# PortBreakoutCapacitive_r2.net
KiCad netlist of a schematic drawn in EAGLE
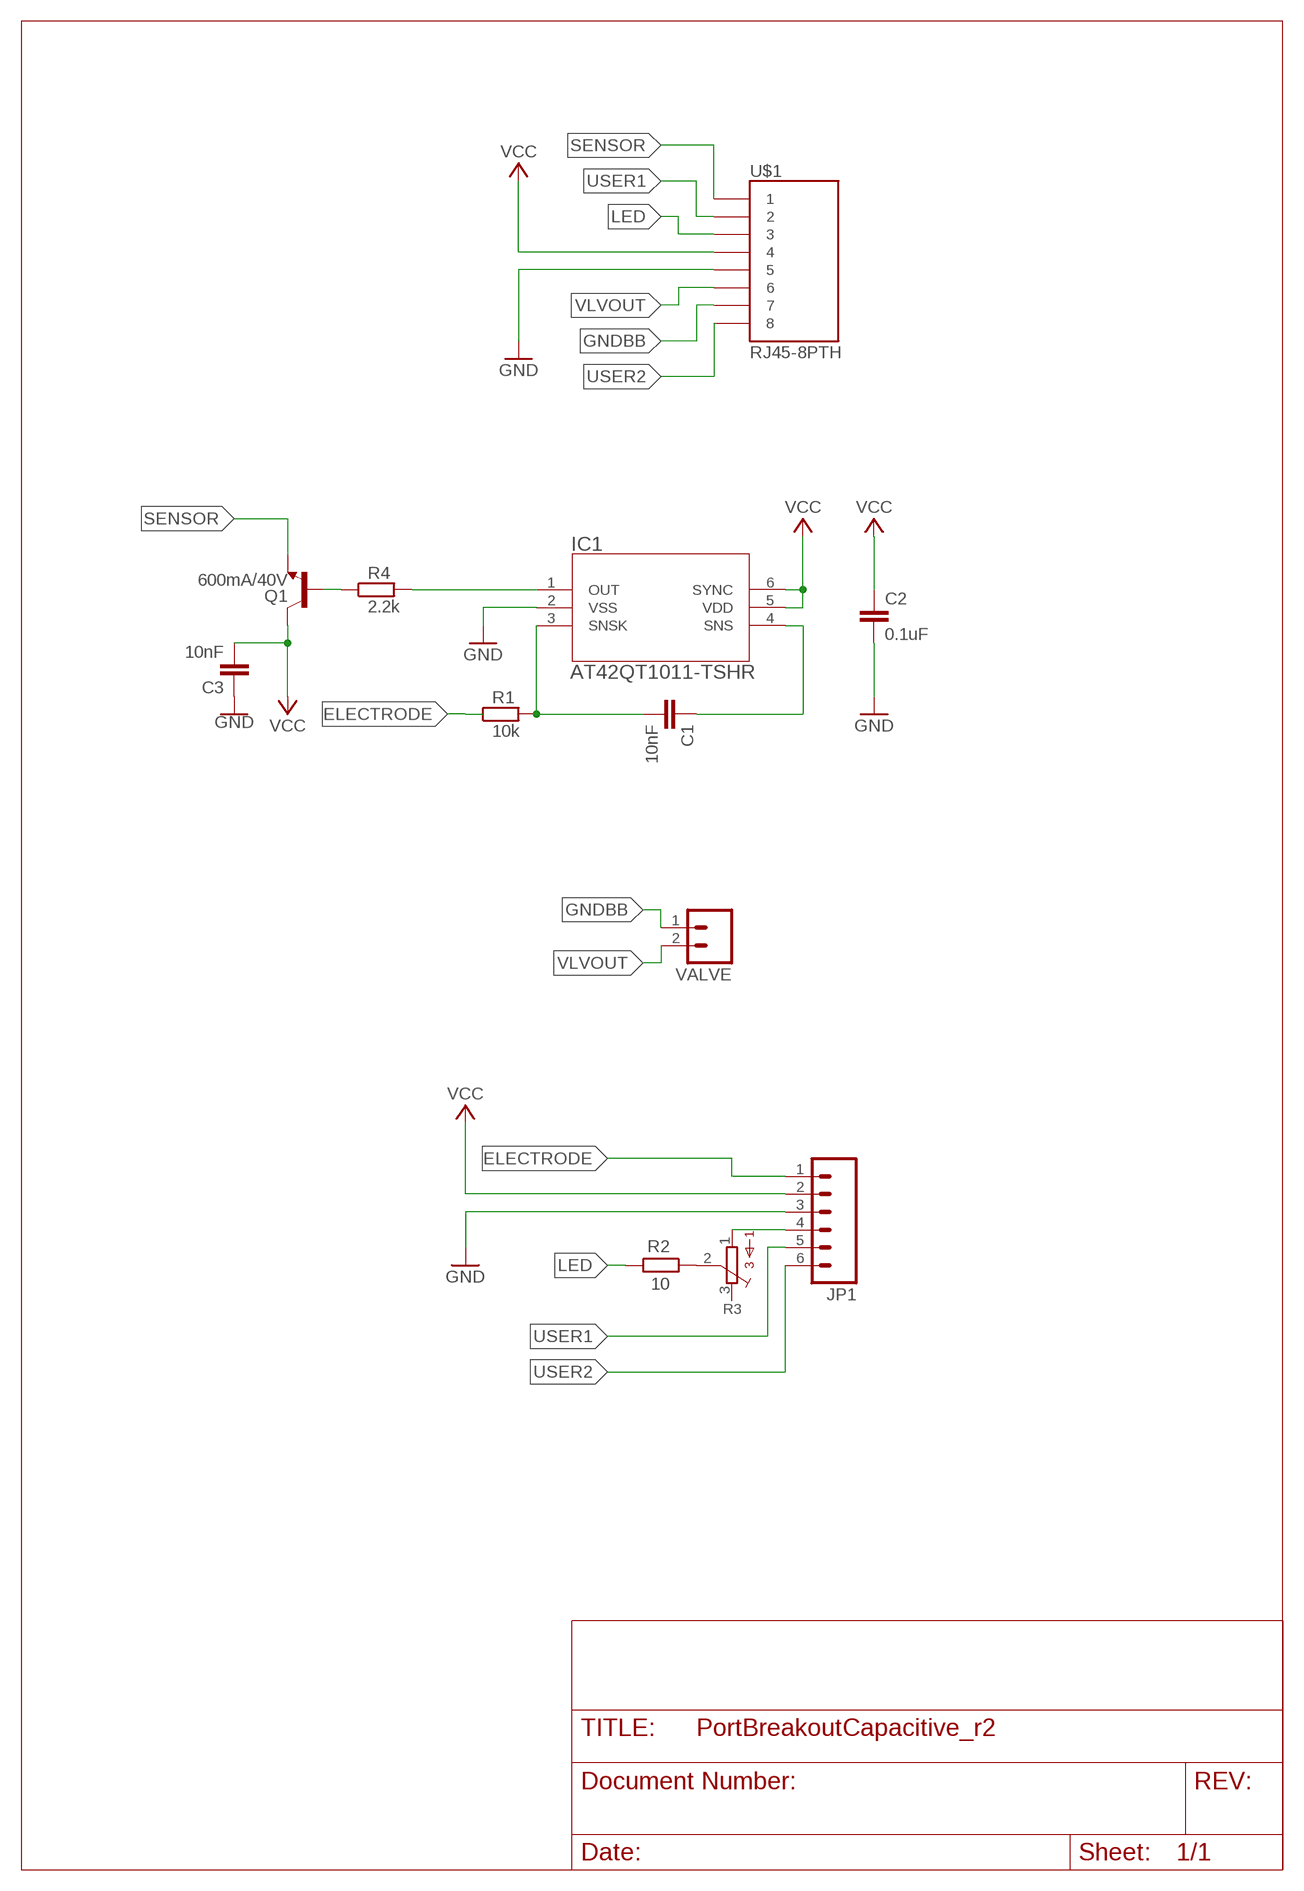
[diagram p0: schematic, sheet 1]

(export (version "E")
  (design (tool "Eeschema 10.0.6"))
  (components
    (comp (ref "C1")
      (value "10nF")
      (footprint "eagle-import:C1206")
      (libsource (lib "eagle-import") (part "C-EUC1206"))
    )
    (comp (ref "C2")
      (value "0.1uF")
      (footprint "eagle-import:C1206")
      (libsource (lib "eagle-import") (part "C-EUC1206"))
    )
    (comp (ref "C3")
      (value "10nF")
      (footprint "eagle-import:C1206")
      (libsource (lib "eagle-import") (part "C-EUC1206"))
    )
    (comp (ref "IC1")
      (value "AT42QT1011-TSHR")
      (footprint "eagle-import:6ST1_ATM")
      (fields (field (name "MANUFACTURER_PART_NUMBER") "AT42QT1010-TSHR"))
      (libsource (lib "eagle-import") (part "AT42QT1010-TSHR"))
    )
    (comp (ref "JP1")
      (value "M063.5MM-6")
      (footprint "eagle-import:SCREWTERMINAL-3.5MM-6")
      (libsource (lib "eagle-import") (part "M063.5MM-6"))
    )
    (comp (ref "Q1")
      (value "600mA/40V")
      (footprint "eagle-import:SOT23-3")
      (libsource (lib "eagle-import") (part "TRANS_NPN-MMBT2222AL"))
    )
    (comp (ref "R1")
      (value "10k")
      (footprint "eagle-import:R1206")
      (libsource (lib "eagle-import") (part "R-EU_R1206"))
    )
    (comp (ref "R2")
      (value "10")
      (footprint "eagle-import:R1206")
      (libsource (lib "eagle-import") (part "R-EU_R1206"))
    )
    (comp (ref "R3")
      (value "3362R")
      (footprint "eagle-import:3362R")
      (libsource (lib "eagle-import") (part "3362R"))
    )
    (comp (ref "R4")
      (value "2.2k")
      (footprint "eagle-import:R1206")
      (libsource (lib "eagle-import") (part "R-EU_R1206"))
    )
    (comp (ref "U$1")
      (value "RJ45-8PTH")
      (footprint "eagle-import:RJ45-8")
      (libsource (lib "eagle-import") (part "RJ45-8PTH"))
    )
    (comp (ref "VALVE")
      (value "M023.5MM_LOCK")
      (footprint "eagle-import:SCREWTERMINAL-3.5MM-2_LOCK")
      (libsource (lib "eagle-import") (part "M023.5MM_LOCK"))
    )
  )
  (nets
    (net (code "1") (name "ELECTRODE") (class "Default")
      (node (ref "JP1") (pin "1") (pinfunction "1_1") (pintype "passive"))
      (node (ref "R1") (pin "1") (pinfunction "1_1") (pintype "passive"))
    )
    (net (code "2") (name "GND") (class "Default")
      (node (ref "C2") (pin "2") (pinfunction "2_2") (pintype "passive"))
      (node (ref "C3") (pin "1") (pinfunction "1_1") (pintype "passive"))
      (node (ref "IC1") (pin "2") (pinfunction "VSS_2") (pintype "power_in"))
      (node (ref "JP1") (pin "3") (pinfunction "3_3") (pintype "passive"))
      (node (ref "U$1") (pin "5") (pinfunction "5_5") (pintype "bidirectional"))
    )
    (net (code "3") (name "GNDBB") (class "Default")
      (node (ref "U$1") (pin "7") (pinfunction "7_7") (pintype "bidirectional"))
      (node (ref "VALVE") (pin "1") (pinfunction "1_1") (pintype "passive"))
    )
    (net (code "4") (name "LED") (class "Default")
      (node (ref "R2") (pin "2") (pinfunction "2_2") (pintype "passive"))
      (node (ref "U$1") (pin "3") (pinfunction "3_3") (pintype "bidirectional"))
    )
    (net (code "5") (name "Net-(IC1-OUT)") (class "Default")
      (node (ref "IC1") (pin "1") (pinfunction "OUT_1") (pintype "output"))
      (node (ref "R4") (pin "2") (pinfunction "2_2") (pintype "passive"))
    )
    (net (code "6") (name "Net-(IC1-SNS)") (class "Default")
      (node (ref "C1") (pin "1") (pinfunction "1_1") (pintype "passive"))
      (node (ref "IC1") (pin "4") (pinfunction "SNS_4") (pintype "bidirectional"))
    )
    (net (code "7") (name "Net-(IC1-SNSK)") (class "Default")
      (node (ref "C1") (pin "2") (pinfunction "2_2") (pintype "passive"))
      (node (ref "IC1") (pin "3") (pinfunction "SNSK_3") (pintype "bidirectional"))
      (node (ref "R1") (pin "2") (pinfunction "2_2") (pintype "passive"))
    )
    (net (code "8") (name "Net-(JP1-Pad4)") (class "Default")
      (node (ref "JP1") (pin "4") (pinfunction "4_4") (pintype "passive"))
      (node (ref "R3") (pin "1") (pinfunction "1_1") (pintype "passive"))
    )
    (net (code "9") (name "Net-(Q1-B)") (class "Default")
      (node (ref "Q1") (pin "1") (pinfunction "B_1") (pintype "passive"))
      (node (ref "R4") (pin "1") (pinfunction "1_1") (pintype "passive"))
    )
    (net (code "10") (name "Net-(R2-Pad1)") (class "Default")
      (node (ref "R2") (pin "1") (pinfunction "1_1") (pintype "passive"))
      (node (ref "R3") (pin "2") (pinfunction "2_2") (pintype "passive"))
    )
    (net (code "11") (name "SENSOR") (class "Default")
      (node (ref "Q1") (pin "2") (pinfunction "E_2") (pintype "passive"))
      (node (ref "U$1") (pin "1") (pinfunction "1_1") (pintype "bidirectional"))
    )
    (net (code "12") (name "USER1") (class "Default")
      (node (ref "JP1") (pin "5") (pinfunction "5_5") (pintype "passive"))
      (node (ref "U$1") (pin "2") (pinfunction "2_2") (pintype "bidirectional"))
    )
    (net (code "13") (name "USER2") (class "Default")
      (node (ref "JP1") (pin "6") (pinfunction "6_6") (pintype "passive"))
      (node (ref "U$1") (pin "8") (pinfunction "8_8") (pintype "bidirectional"))
    )
    (net (code "14") (name "VCC") (class "Default")
      (node (ref "C2") (pin "1") (pinfunction "1_1") (pintype "passive"))
      (node (ref "C3") (pin "2") (pinfunction "2_2") (pintype "passive"))
      (node (ref "IC1") (pin "5") (pinfunction "VDD_5") (pintype "power_in"))
      (node (ref "IC1") (pin "6") (pinfunction "SYNC_6") (pintype "input"))
      (node (ref "JP1") (pin "2") (pinfunction "2_2") (pintype "passive"))
      (node (ref "Q1") (pin "3") (pinfunction "C_3") (pintype "passive"))
      (node (ref "U$1") (pin "4") (pinfunction "4_4") (pintype "bidirectional"))
    )
    (net (code "15") (name "VLVOUT") (class "Default")
      (node (ref "U$1") (pin "6") (pinfunction "6_6") (pintype "bidirectional"))
      (node (ref "VALVE") (pin "2") (pinfunction "2_2") (pintype "passive"))
    )
    (net (code "16") (name "unconnected-(R3-Pad3)") (class "Default")
      (node (ref "R3") (pin "3") (pinfunction "3_3") (pintype "passive"))
    )
  )
)
